# LeiraBoard.net
KiCad netlist of a schematic drawn in EAGLE
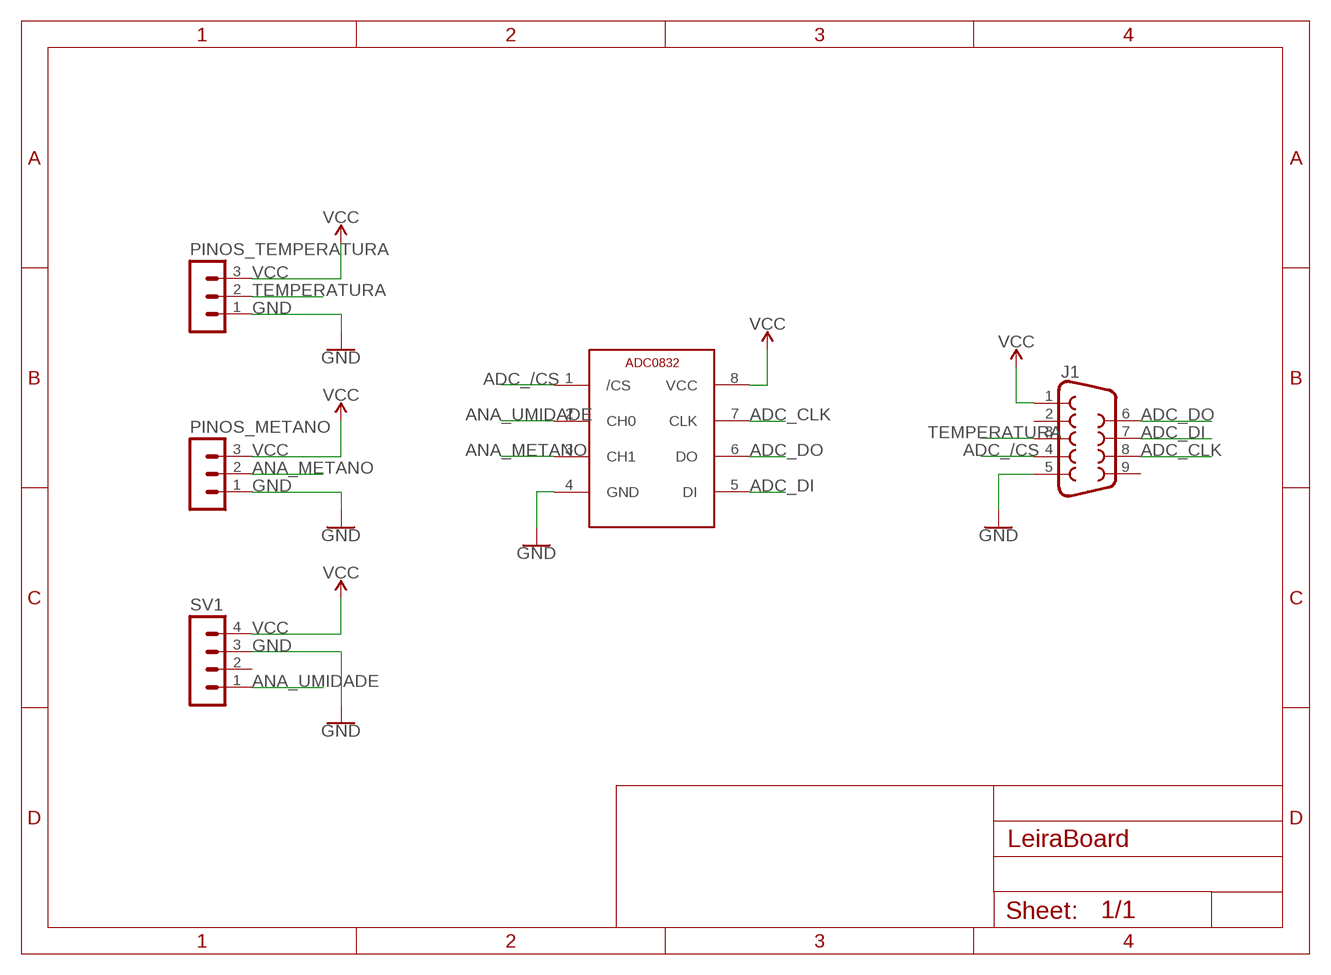
[diagram p0: schematic, sheet 1]

(export (version "E")
  (design (tool "Eeschema 10.0.6"))
  (components
    (comp (ref "J1")
      (value "DB9MALE")
      (footprint "eagle-import:DB9_MALE")
      (libsource (lib "eagle-import") (part "DB9MALE"))
    )
    (comp (ref "PINOS_METANO")
      (value "MA03-1")
      (footprint "eagle-import:MA03-1")
      (libsource (lib "eagle-import") (part "MA03-1"))
    )
    (comp (ref "PINOS_TEMPERATURA")
      (value "MA03-1")
      (footprint "eagle-import:MA03-1")
      (libsource (lib "eagle-import") (part "MA03-1"))
    )
    (comp (ref "SV1")
      (value "MA04-1")
      (footprint "eagle-import:MA04-1")
      (libsource (lib "eagle-import") (part "MA04-1"))
    )
    (comp (ref "U$1")
      (value "ADC8032")
      (footprint "eagle-import:DIL8")
      (libsource (lib "eagle-import") (part "ADC8032"))
    )
  )
  (nets
    (net (code "1") (name "/ADC_CLK") (class "Default")
      (node (ref "J1") (pin "8") (pinfunction "8_8") (pintype "passive"))
      (node (ref "U$1") (pin "7") (pinfunction "CLK_7") (pintype "bidirectional"))
    )
    (net (code "2") (name "/ADC_DI") (class "Default")
      (node (ref "J1") (pin "7") (pinfunction "7_7") (pintype "passive"))
      (node (ref "U$1") (pin "5") (pinfunction "DI_5") (pintype "bidirectional"))
    )
    (net (code "3") (name "/ADC_DO") (class "Default")
      (node (ref "J1") (pin "6") (pinfunction "6_6") (pintype "passive"))
      (node (ref "U$1") (pin "6") (pinfunction "DO_6") (pintype "bidirectional"))
    )
    (net (code "4") (name "/ADC_{slash}CS") (class "Default")
      (node (ref "J1") (pin "4") (pinfunction "4_4") (pintype "passive"))
      (node (ref "U$1") (pin "1") (pinfunction "/CS_1") (pintype "bidirectional"))
    )
    (net (code "5") (name "/ANA_METANO") (class "Default")
      (node (ref "PINOS_METANO") (pin "2") (pinfunction "2_2") (pintype "passive"))
      (node (ref "U$1") (pin "3") (pinfunction "CH1_3") (pintype "bidirectional"))
    )
    (net (code "6") (name "/ANA_UMIDADE") (class "Default")
      (node (ref "SV1") (pin "1") (pinfunction "1_1") (pintype "passive"))
      (node (ref "U$1") (pin "2") (pinfunction "CH0_2") (pintype "bidirectional"))
    )
    (net (code "7") (name "/TEMPERATURA") (class "Default")
      (node (ref "J1") (pin "3") (pinfunction "3_3") (pintype "passive"))
      (node (ref "PINOS_TEMPERATURA") (pin "2") (pinfunction "2_2") (pintype "passive"))
    )
    (net (code "8") (name "GND") (class "Default")
      (node (ref "J1") (pin "5") (pinfunction "5_5") (pintype "passive"))
      (node (ref "PINOS_METANO") (pin "1") (pinfunction "1_1") (pintype "passive"))
      (node (ref "PINOS_TEMPERATURA") (pin "1") (pinfunction "1_1") (pintype "passive"))
      (node (ref "SV1") (pin "3") (pinfunction "3_3") (pintype "passive"))
      (node (ref "U$1") (pin "4") (pinfunction "GND_4") (pintype "bidirectional"))
    )
    (net (code "9") (name "VCC") (class "Default")
      (node (ref "J1") (pin "1") (pinfunction "1_1") (pintype "passive"))
      (node (ref "PINOS_METANO") (pin "3") (pinfunction "3_3") (pintype "passive"))
      (node (ref "PINOS_TEMPERATURA") (pin "3") (pinfunction "3_3") (pintype "passive"))
      (node (ref "SV1") (pin "4") (pinfunction "4_4") (pintype "passive"))
      (node (ref "U$1") (pin "8") (pinfunction "VCC_8") (pintype "bidirectional"))
    )
    (net (code "10") (name "unconnected-(J1-Pad2)") (class "Default")
      (node (ref "J1") (pin "2") (pinfunction "2_2") (pintype "passive"))
    )
    (net (code "11") (name "unconnected-(J1-Pad9)") (class "Default")
      (node (ref "J1") (pin "9") (pinfunction "9_9") (pintype "passive"))
    )
    (net (code "12") (name "unconnected-(SV1-Pad2)") (class "Default")
      (node (ref "SV1") (pin "2") (pinfunction "2_2") (pintype "passive"))
    )
  )
)
